# Power_Monitor.net
KiCad netlist of a schematic drawn in Altium Designer
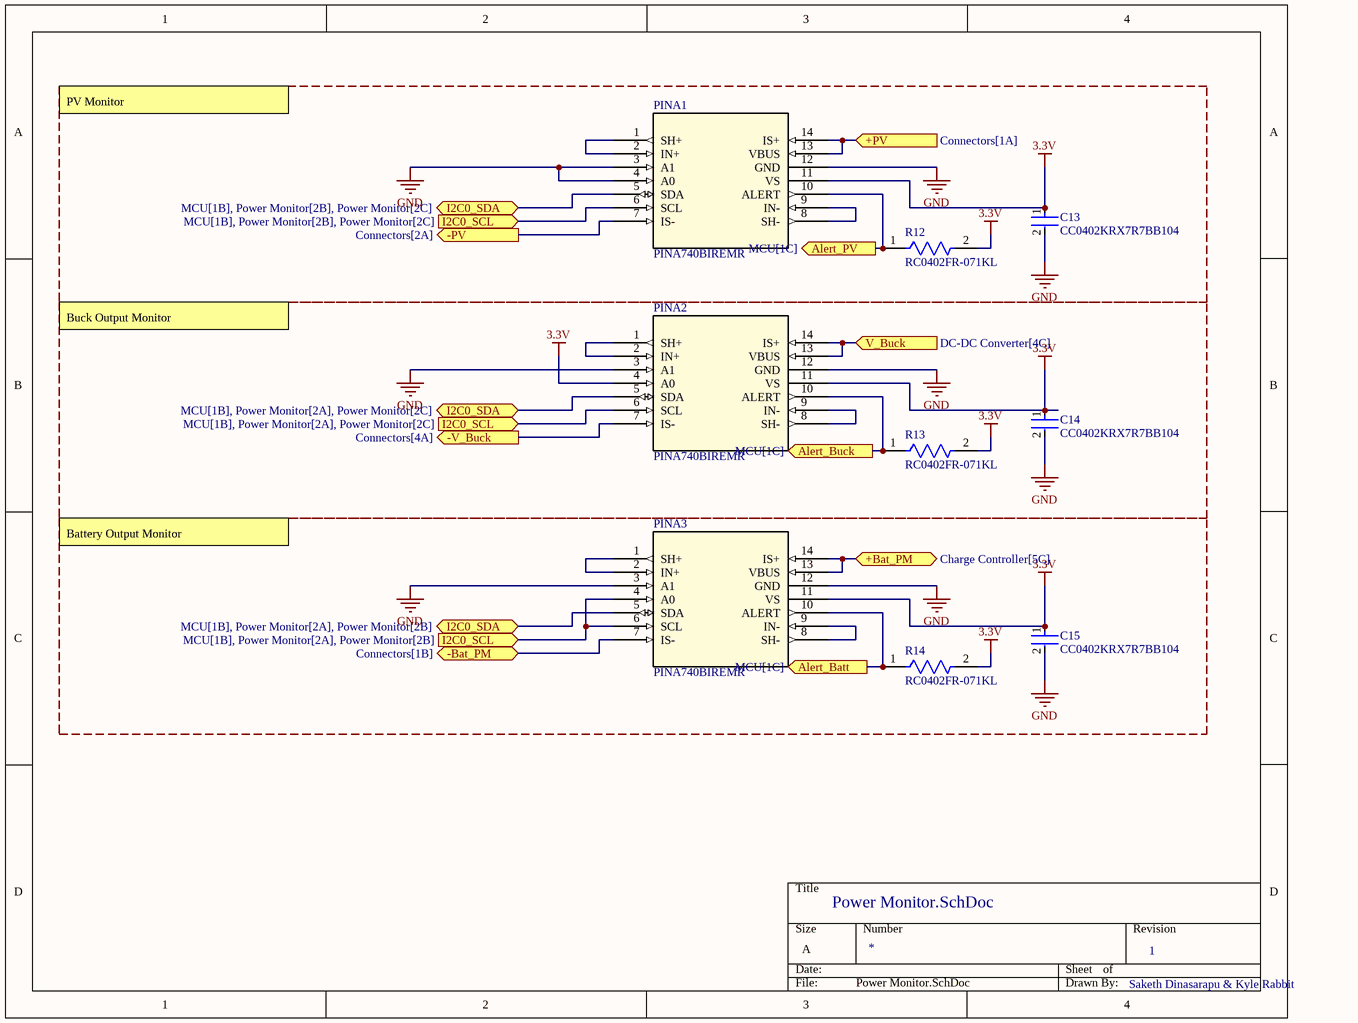
[diagram p0: Power Monitor.SchDoc]

(export (version "E")
  (design (tool "Eeschema 10.0.6"))
  (components
    (comp (ref "C13")
      (value "CC0402KRX7R7BB104")
      (footprint "FP-CC0402-MFG")
      (description "CAP CER 0.1UF 16V X7R 0402")
      (fields (field (name "MANUFACTURER") "YAGEO") (field (name "TOLERANCE") "0.1"))
      (libsource (lib "Altium Content Vault") (part "11868f565c42a9108669ba33697ecf6"))
    )
    (comp (ref "C14")
      (value "CC0402KRX7R7BB104")
      (footprint "FP-CC0402-MFG")
      (description "CAP CER 0.1UF 16V X7R 0402")
      (fields (field (name "MANUFACTURER") "YAGEO") (field (name "TOLERANCE") "0.1"))
      (libsource (lib "Altium Content Vault") (part "11868f565c42a9108669ba33697ecf6"))
    )
    (comp (ref "C15")
      (value "CC0402KRX7R7BB104")
      (footprint "FP-CC0402-MFG")
      (description "CAP CER 0.1UF 16V X7R 0402")
      (fields (field (name "MANUFACTURER") "YAGEO") (field (name "TOLERANCE") "0.1"))
      (libsource (lib "Altium Content Vault") (part "11868f565c42a9108669ba33697ecf6"))
    )
    (comp (ref "PINA1")
      (value "PINA740BIREMR")
      (footprint "VQFN14_REM_TEX")
      (description "No Description Available")
      (libsource (lib "PINA740BIREMR") (part "PINA740BIREMR"))
    )
    (comp (ref "PINA2")
      (value "PINA740BIREMR")
      (footprint "VQFN14_REM_TEX")
      (description "No Description Available")
      (libsource (lib "PINA740BIREMR") (part "PINA740BIREMR"))
    )
    (comp (ref "PINA3")
      (value "PINA740BIREMR")
      (footprint "VQFN14_REM_TEX")
      (description "No Description Available")
      (libsource (lib "PINA740BIREMR") (part "PINA740BIREMR"))
    )
    (comp (ref "R12")
      (value "RC0402FR-071KL")
      (footprint "FP-RC0402-0_4-IPC_A")
      (description "RES 1K OHM 1% 1/16W 0402")
      (fields (field (name "TOLERANCE") "1%"))
      (libsource (lib "Altium Content Vault") (part "1029c3af85768c4190bb7ad29bc67b5"))
    )
    (comp (ref "R13")
      (value "RC0402FR-071KL")
      (footprint "FP-RC0402-0_4-IPC_A")
      (description "RES 1K OHM 1% 1/16W 0402")
      (fields (field (name "TOLERANCE") "1%"))
      (libsource (lib "Altium Content Vault") (part "1029c3af85768c4190bb7ad29bc67b5"))
    )
    (comp (ref "R14")
      (value "RC0402FR-071KL")
      (footprint "FP-RC0402-0_4-IPC_A")
      (description "RES 1K OHM 1% 1/16W 0402")
      (fields (field (name "TOLERANCE") "1%"))
      (libsource (lib "Altium Content Vault") (part "1029c3af85768c4190bb7ad29bc67b5"))
    )
  )
  (nets
    (net (code "1") (name "/+Bat_PM") (class "Default")
      (node (ref "PINA3") (pin "13") (pinfunction "VBUS_13") (pintype "input"))
      (node (ref "PINA3") (pin "14") (pinfunction "IS+_14") (pintype "input"))
    )
    (net (code "2") (name "/+PV") (class "Default")
      (node (ref "PINA1") (pin "13") (pinfunction "VBUS_13") (pintype "input"))
      (node (ref "PINA1") (pin "14") (pinfunction "IS+_14") (pintype "input"))
    )
    (net (code "3") (name "/-Bat_PM") (class "Default")
      (node (ref "PINA3") (pin "7") (pinfunction "IS-_7") (pintype "input"))
    )
    (net (code "4") (name "/-PV") (class "Default")
      (node (ref "PINA1") (pin "7") (pinfunction "IS-_7") (pintype "input"))
    )
    (net (code "5") (name "/-V_Buck") (class "Default")
      (node (ref "PINA2") (pin "7") (pinfunction "IS-_7") (pintype "input"))
    )
    (net (code "6") (name "/Alert_Batt") (class "Default")
      (node (ref "PINA3") (pin "10") (pinfunction "ALERT_10") (pintype "output"))
      (node (ref "R14") (pin "1") (pinfunction "1_1") (pintype "passive"))
    )
    (net (code "7") (name "/Alert_Buck") (class "Default")
      (node (ref "PINA2") (pin "10") (pinfunction "ALERT_10") (pintype "output"))
      (node (ref "R13") (pin "1") (pinfunction "1_1") (pintype "passive"))
    )
    (net (code "8") (name "/Alert_PV") (class "Default")
      (node (ref "PINA1") (pin "10") (pinfunction "ALERT_10") (pintype "output"))
      (node (ref "R12") (pin "1") (pinfunction "1_1") (pintype "passive"))
    )
    (net (code "9") (name "/I2C0_SCL") (class "Default")
      (node (ref "PINA1") (pin "6") (pinfunction "SCL_6") (pintype "input"))
      (node (ref "PINA2") (pin "6") (pinfunction "SCL_6") (pintype "input"))
      (node (ref "PINA3") (pin "4") (pinfunction "A0_4") (pintype "input"))
      (node (ref "PINA3") (pin "6") (pinfunction "SCL_6") (pintype "input"))
    )
    (net (code "10") (name "/I2C0_SDA") (class "Default")
      (node (ref "PINA1") (pin "5") (pinfunction "SDA_5") (pintype "bidirectional"))
      (node (ref "PINA2") (pin "5") (pinfunction "SDA_5") (pintype "bidirectional"))
      (node (ref "PINA3") (pin "5") (pinfunction "SDA_5") (pintype "bidirectional"))
    )
    (net (code "11") (name "/V_Buck") (class "Default")
      (node (ref "PINA2") (pin "13") (pinfunction "VBUS_13") (pintype "input"))
      (node (ref "PINA2") (pin "14") (pinfunction "IS+_14") (pintype "input"))
    )
    (net (code "12") (name "3.3V") (class "Default")
      (node (ref "C13") (pin "1") (pinfunction "1_1") (pintype "passive"))
      (node (ref "C14") (pin "1") (pinfunction "1_1") (pintype "passive"))
      (node (ref "C15") (pin "1") (pinfunction "1_1") (pintype "passive"))
      (node (ref "PINA1") (pin "11") (pinfunction "VS_11") (pintype "power_in"))
      (node (ref "PINA2") (pin "11") (pinfunction "VS_11") (pintype "power_in"))
      (node (ref "PINA2") (pin "4") (pinfunction "A0_4") (pintype "input"))
      (node (ref "PINA3") (pin "11") (pinfunction "VS_11") (pintype "power_in"))
      (node (ref "R12") (pin "2") (pinfunction "2_2") (pintype "passive"))
      (node (ref "R13") (pin "2") (pinfunction "2_2") (pintype "passive"))
      (node (ref "R14") (pin "2") (pinfunction "2_2") (pintype "passive"))
    )
    (net (code "13") (name "GND") (class "Default")
      (node (ref "C13") (pin "2") (pinfunction "2_2") (pintype "passive"))
      (node (ref "C14") (pin "2") (pinfunction "2_2") (pintype "passive"))
      (node (ref "C15") (pin "2") (pinfunction "2_2") (pintype "passive"))
      (node (ref "PINA1") (pin "12") (pinfunction "GND_12") (pintype "power_in"))
      (node (ref "PINA1") (pin "3") (pinfunction "A1_3") (pintype "input"))
      (node (ref "PINA1") (pin "4") (pinfunction "A0_4") (pintype "input"))
      (node (ref "PINA2") (pin "12") (pinfunction "GND_12") (pintype "power_in"))
      (node (ref "PINA2") (pin "3") (pinfunction "A1_3") (pintype "input"))
      (node (ref "PINA3") (pin "12") (pinfunction "GND_12") (pintype "power_in"))
      (node (ref "PINA3") (pin "3") (pinfunction "A1_3") (pintype "input"))
    )
    (net (code "14") (name "Net-(PINA1-IN+)") (class "Default")
      (node (ref "PINA1") (pin "1") (pinfunction "SH+_1") (pintype "output"))
      (node (ref "PINA1") (pin "2") (pinfunction "IN+_2") (pintype "input"))
    )
    (net (code "15") (name "Net-(PINA1-IN-)") (class "Default")
      (node (ref "PINA1") (pin "8") (pinfunction "SH-_8") (pintype "output"))
      (node (ref "PINA1") (pin "9") (pinfunction "IN-_9") (pintype "input"))
    )
    (net (code "16") (name "Net-(PINA2-IN+)") (class "Default")
      (node (ref "PINA2") (pin "1") (pinfunction "SH+_1") (pintype "output"))
      (node (ref "PINA2") (pin "2") (pinfunction "IN+_2") (pintype "input"))
    )
    (net (code "17") (name "Net-(PINA2-IN-)") (class "Default")
      (node (ref "PINA2") (pin "8") (pinfunction "SH-_8") (pintype "output"))
      (node (ref "PINA2") (pin "9") (pinfunction "IN-_9") (pintype "input"))
    )
    (net (code "18") (name "Net-(PINA3-IN+)") (class "Default")
      (node (ref "PINA3") (pin "1") (pinfunction "SH+_1") (pintype "output"))
      (node (ref "PINA3") (pin "2") (pinfunction "IN+_2") (pintype "input"))
    )
    (net (code "19") (name "Net-(PINA3-IN-)") (class "Default")
      (node (ref "PINA3") (pin "8") (pinfunction "SH-_8") (pintype "output"))
      (node (ref "PINA3") (pin "9") (pinfunction "IN-_9") (pintype "input"))
    )
  )
)
